# artik530_carrierboard.net
KiCad netlist of a schematic drawn in EAGLE
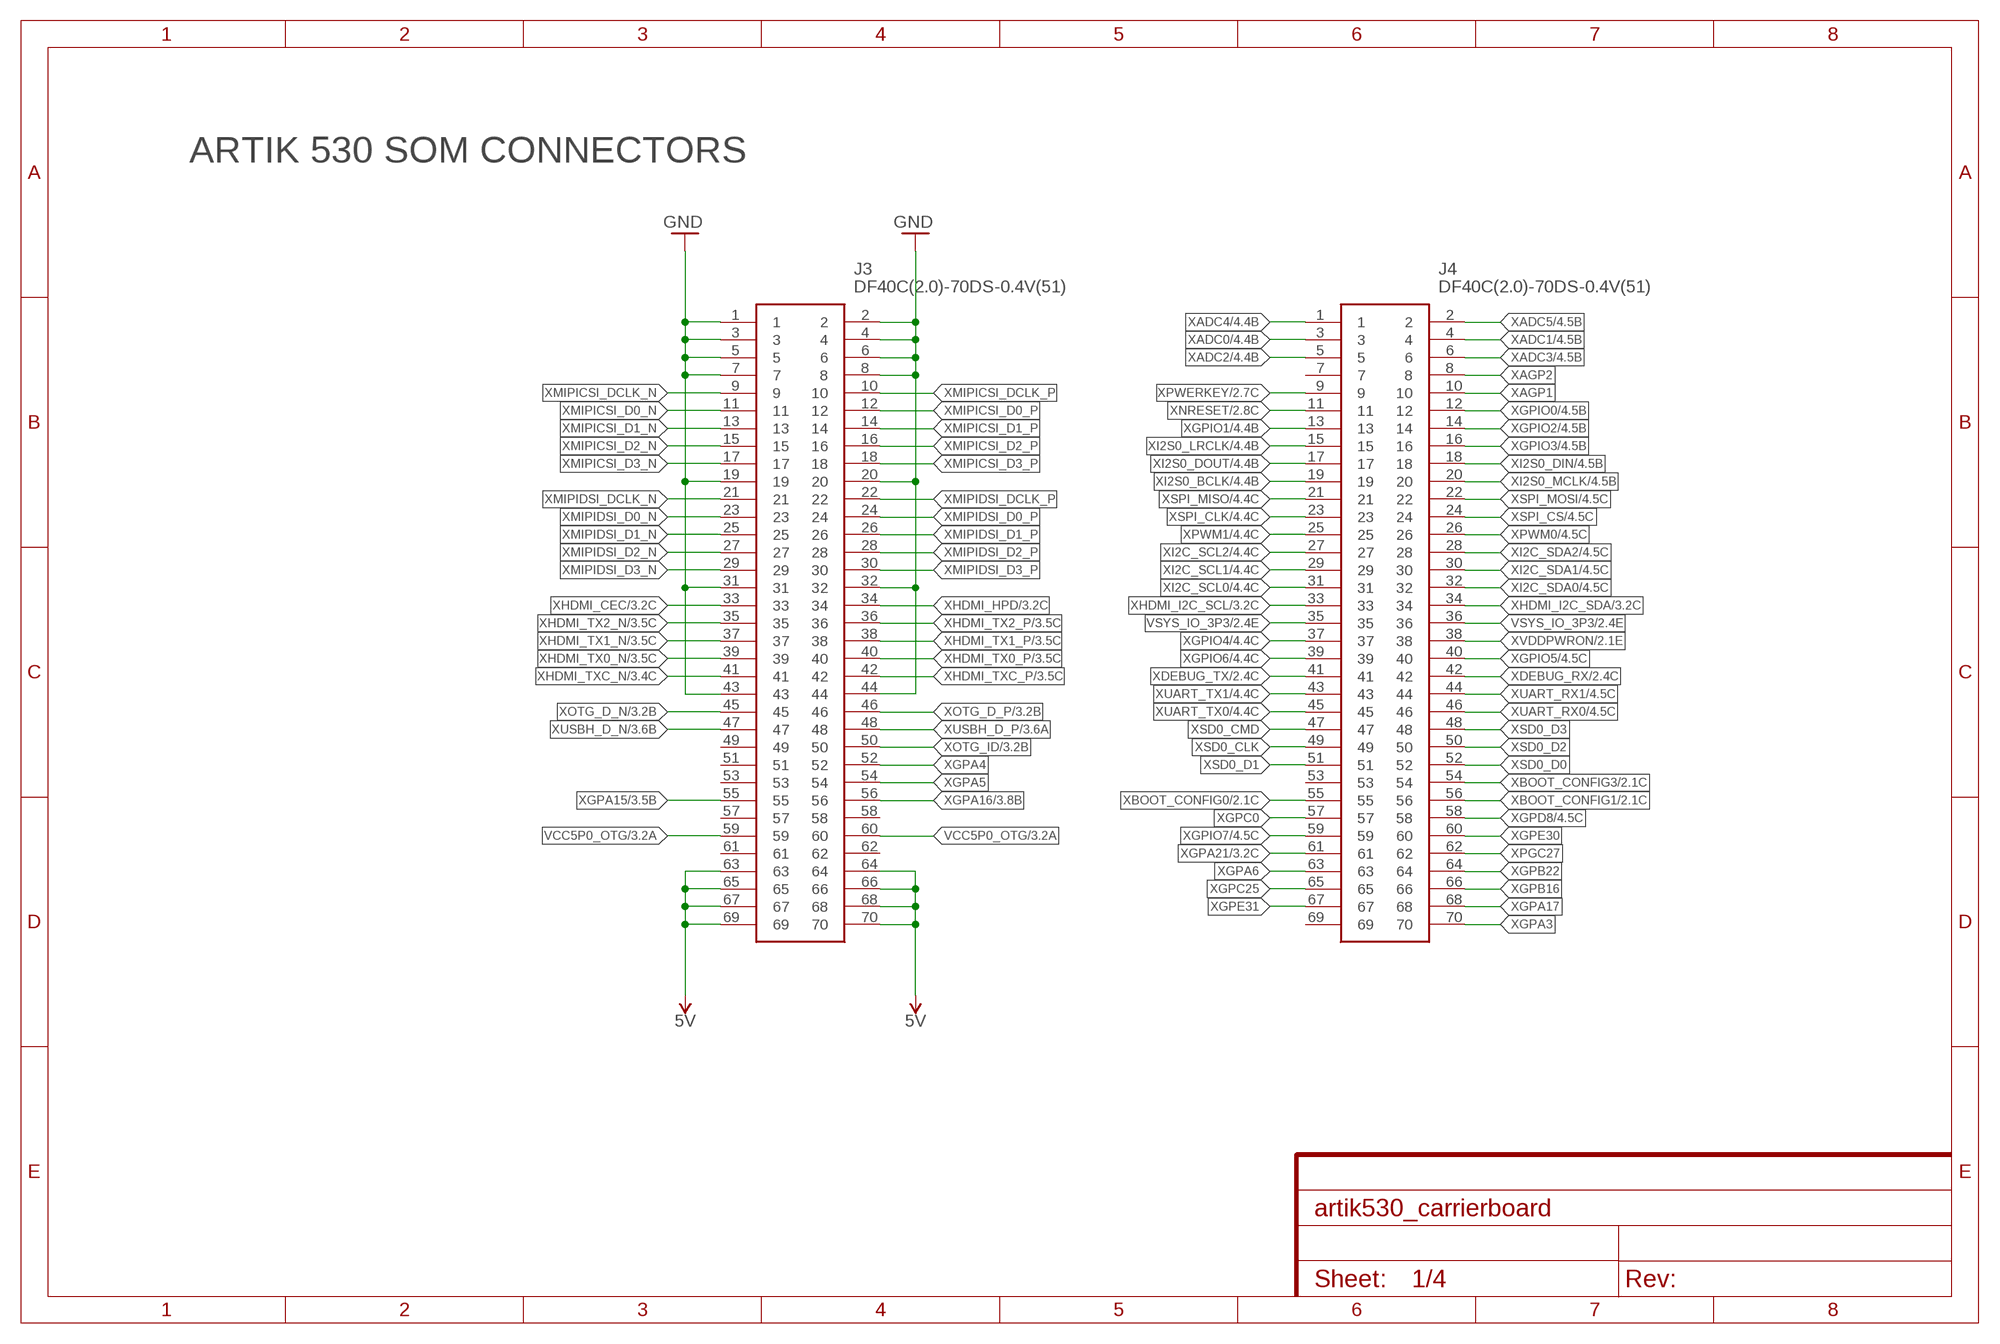
[diagram p0: schematic, sheet 1]
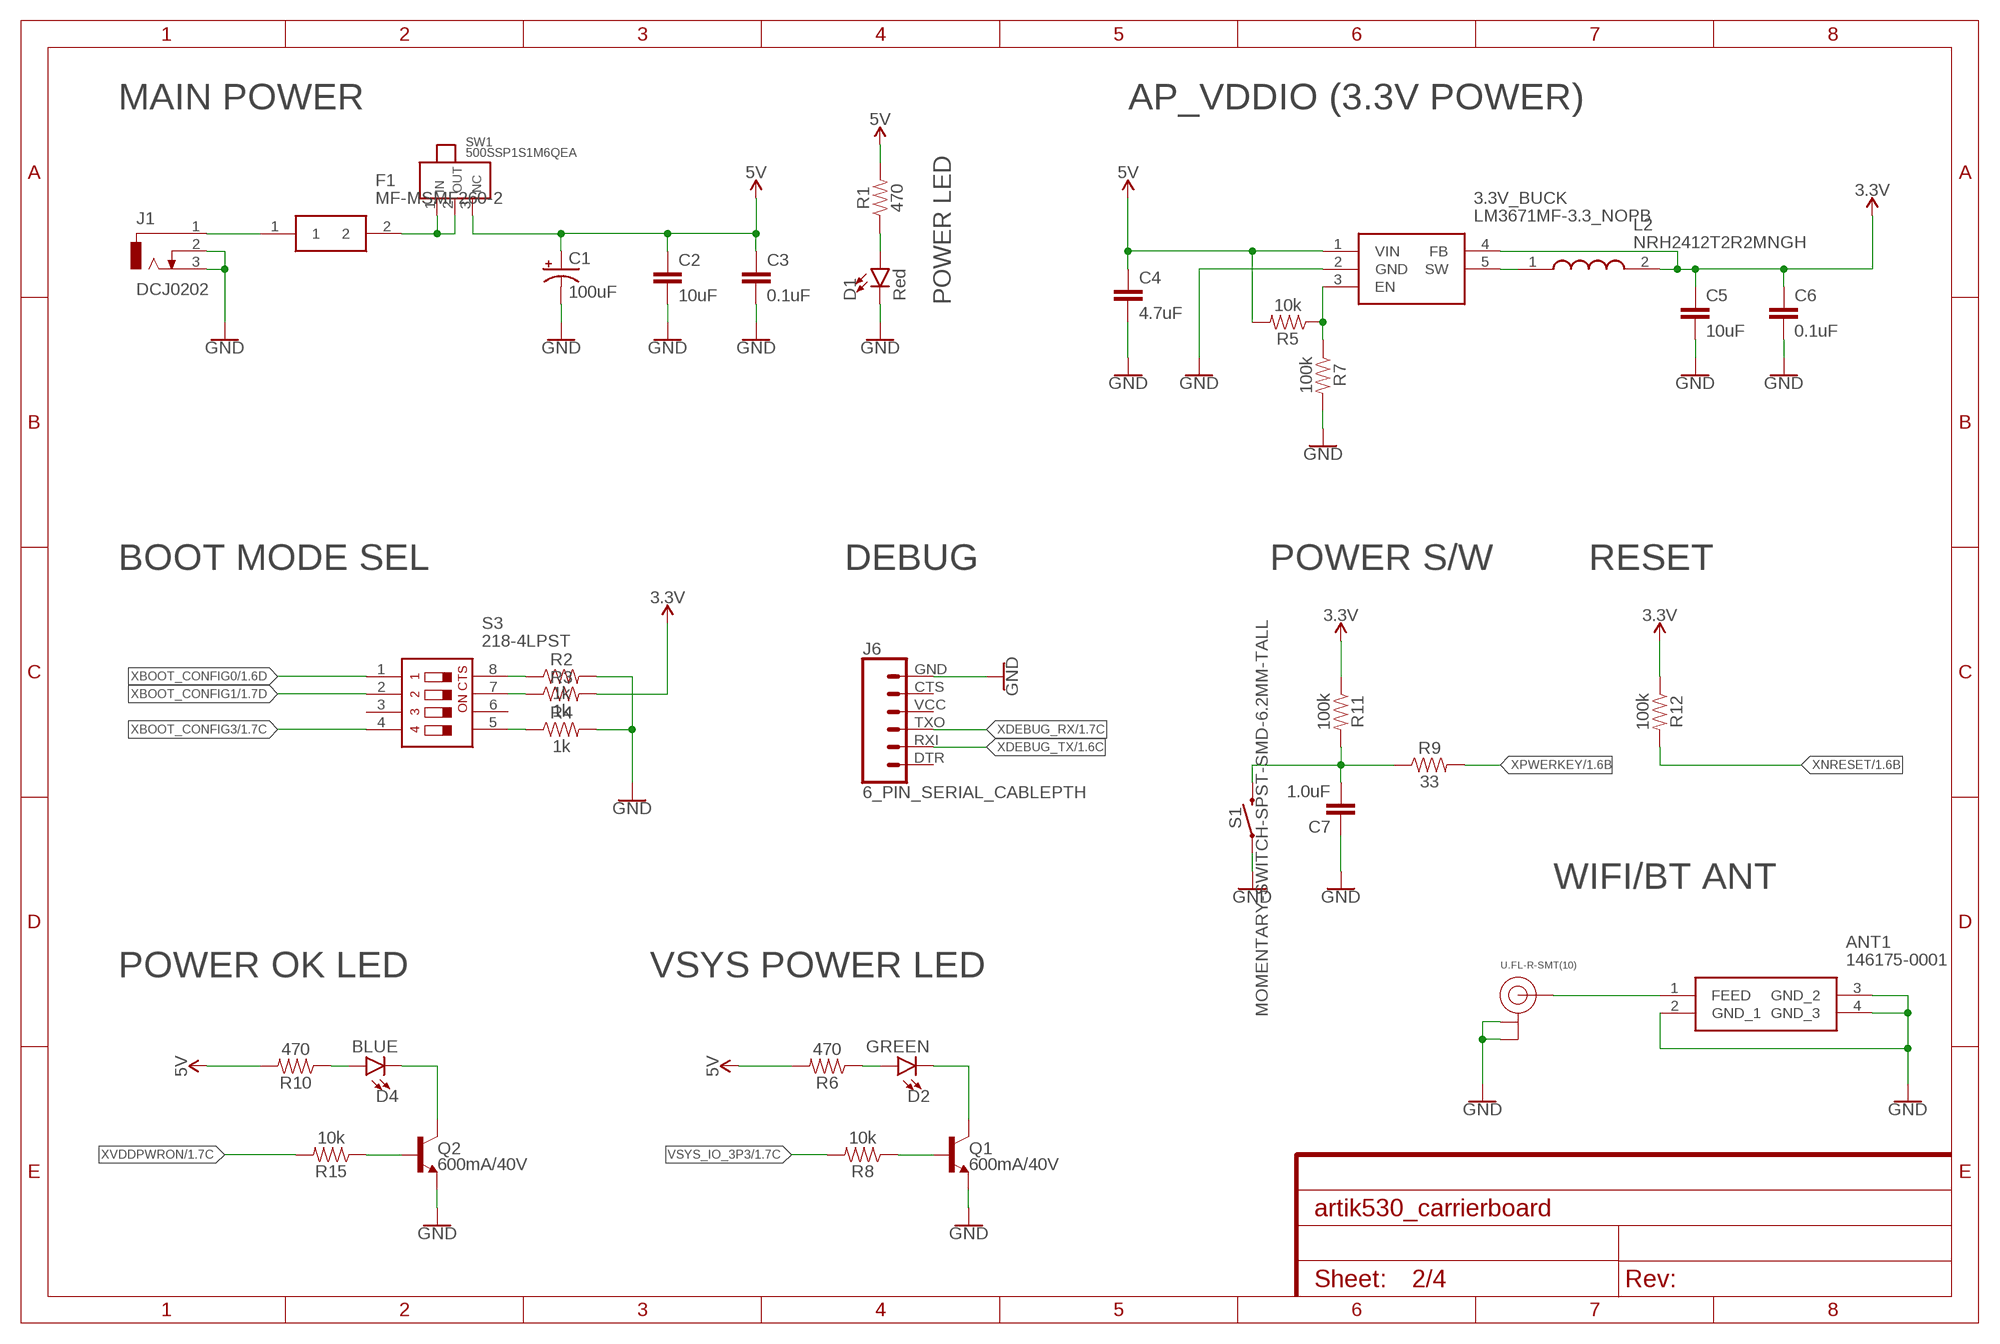
[diagram p1: schematic, sheet 2]
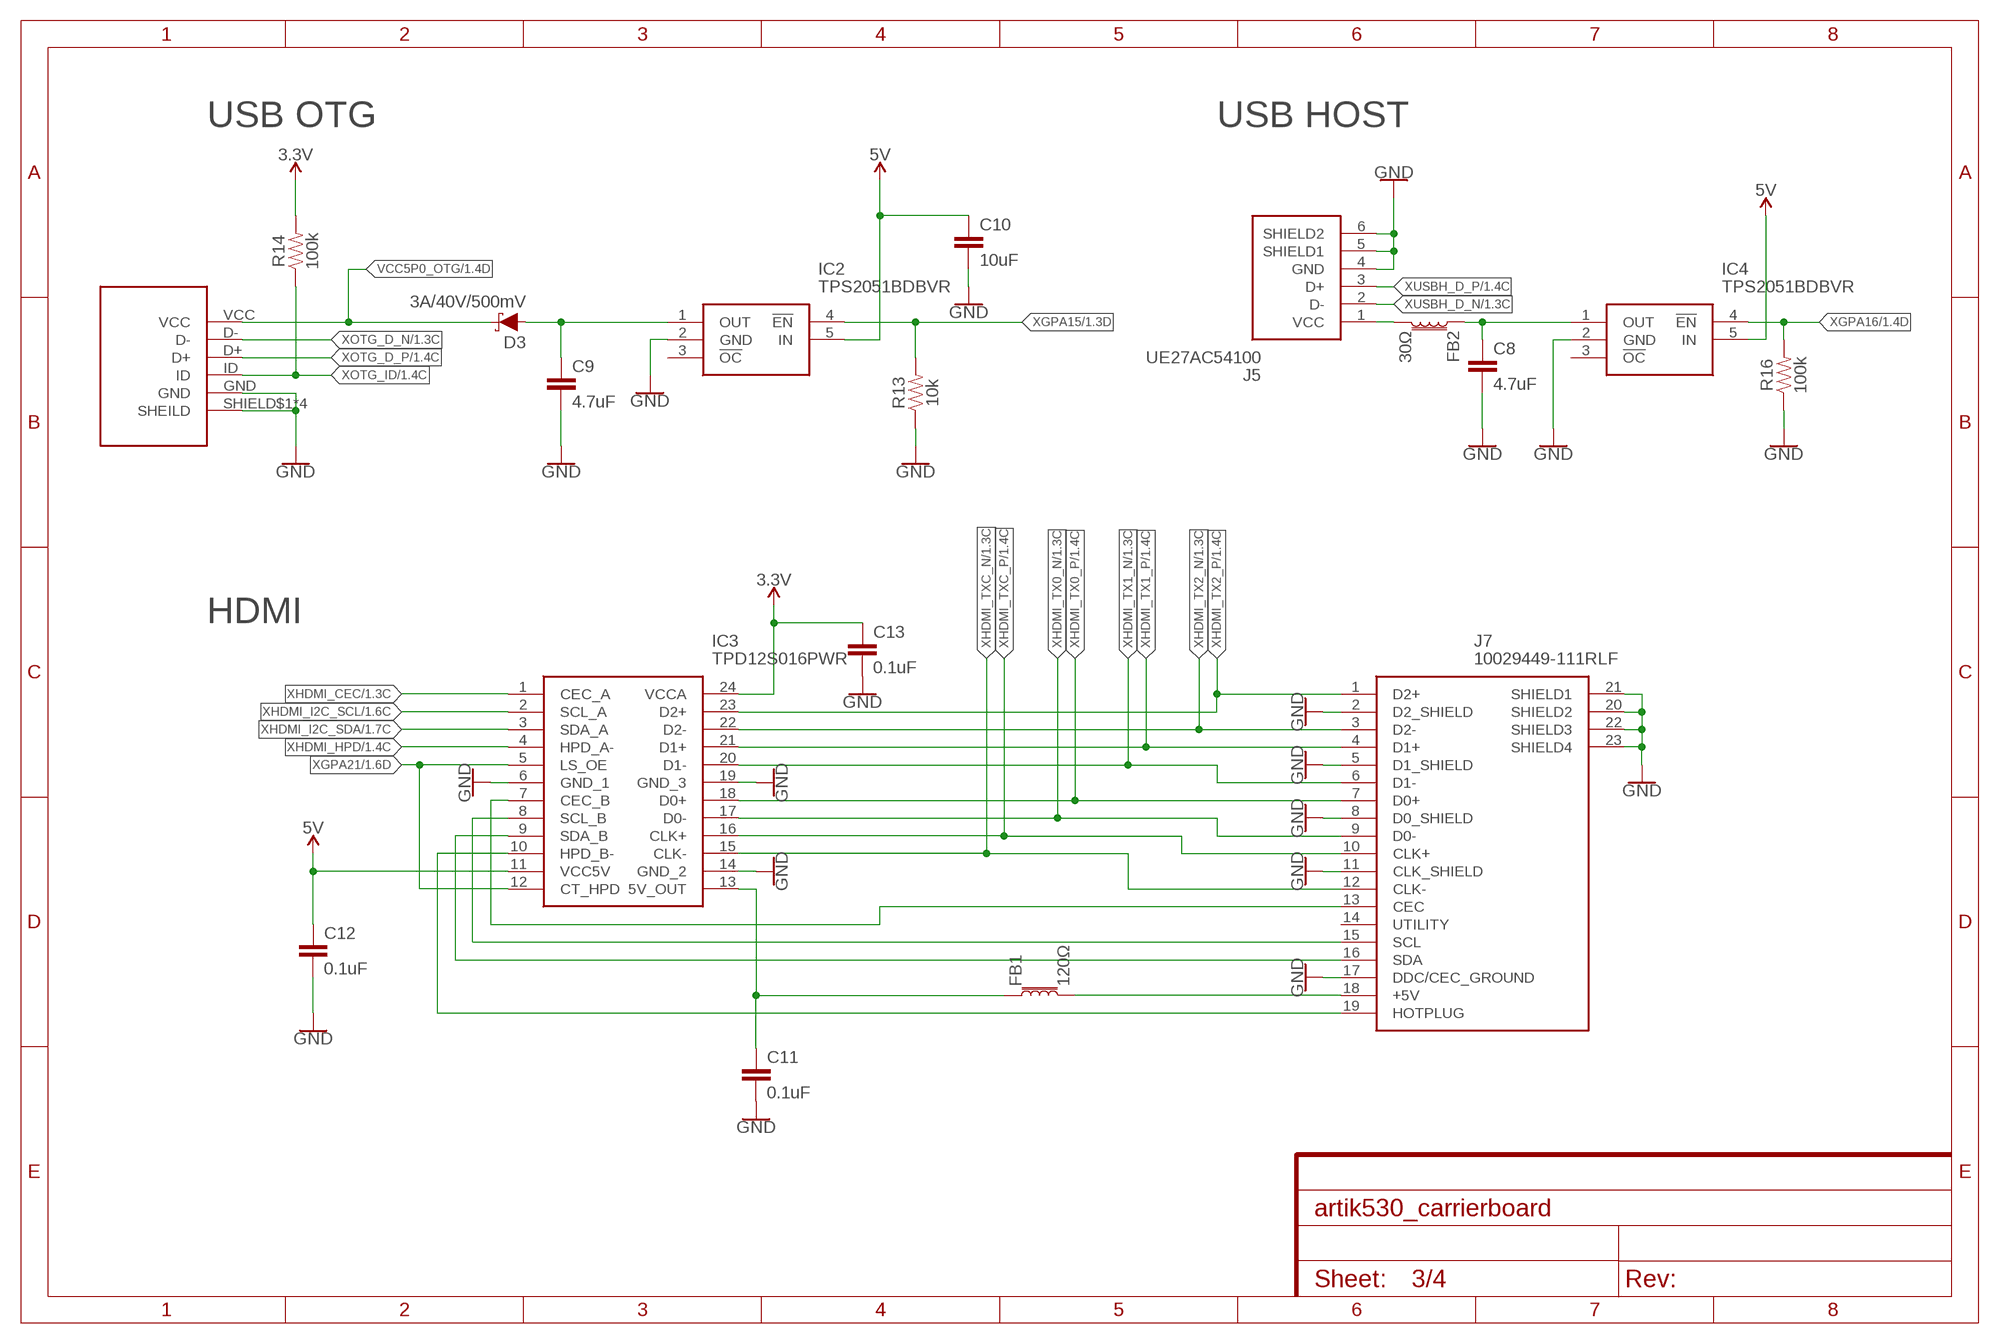
[diagram p2: schematic, sheet 3]
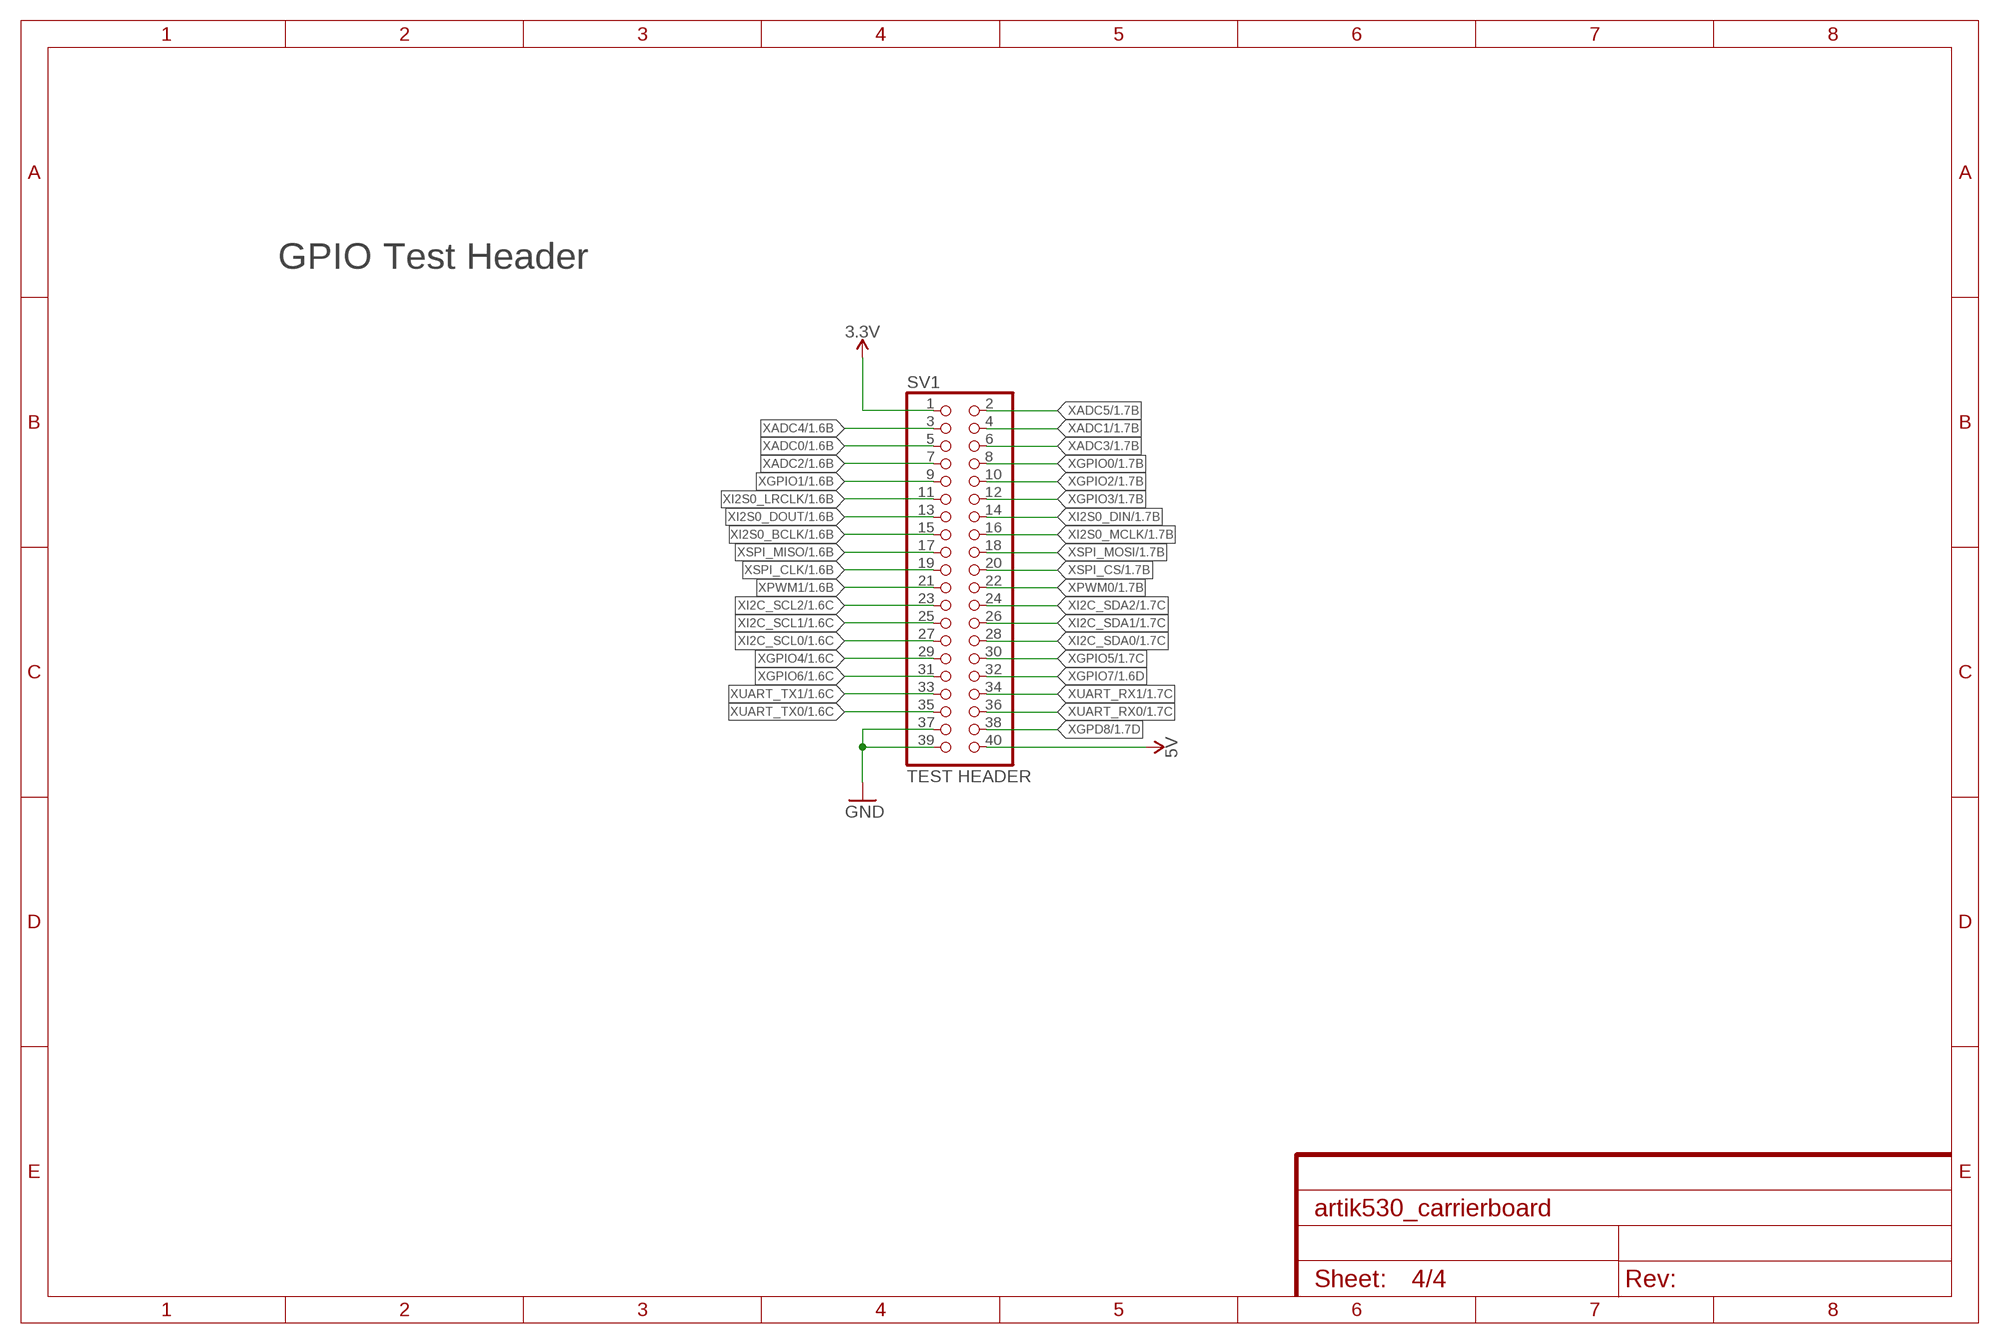
[diagram p3: schematic, sheet 4]

(export (version "E")
  (design (tool "Eeschema 10.0.6"))
  (components
    (comp (ref "3.3V_BUCK")
      (value "LM3671MF-3.3_NOPB")
      (footprint "eagle-import:SOT95P284X122-5N")
      (fields
        (field (name "DIGIKEY_PART_NUMBER") "LM3671MF-3.3/NOPBTR-ND")
        (field (name "MANUFACTURER_PART_NUMBER") "LM3671MF-3.3/NOPB")
      )
      (libsource (lib "eagle-import") (part "LM3671MF-3.3_NOPB"))
    )
    (comp (ref "ANT1")
      (value "146175-0001")
      (footprint "eagle-import:146175-0001")
      (libsource (lib "eagle-import") (part "146175-0001"))
    )
    (comp (ref "C1")
      (value "100uF")
      (footprint "eagle-import:EIA7343")
      (libsource (lib "eagle-import") (part "100UF-POLAR-EIA7343-10V-10%(TANT)"))
    )
    (comp (ref "C2")
      (value "10uF")
      (footprint "eagle-import:0603")
      (libsource (lib "eagle-import") (part "10UF-0603-6.3V-20%"))
    )
    (comp (ref "C3")
      (value "0.1uF")
      (footprint "eagle-import:0603")
      (libsource (lib "eagle-import") (part "0.1UF-0603-25V-(+80/-20%)"))
    )
    (comp (ref "C4")
      (value "4.7uF")
      (footprint "eagle-import:0603")
      (libsource (lib "eagle-import") (part "4.7UF-0603-6.3V-(10%)"))
    )
    (comp (ref "C5")
      (value "10uF")
      (footprint "eagle-import:0603")
      (libsource (lib "eagle-import") (part "10UF-0603-6.3V-20%"))
    )
    (comp (ref "C6")
      (value "0.1uF")
      (footprint "eagle-import:0603")
      (libsource (lib "eagle-import") (part "0.1UF-0603-25V-(+80/-20%)"))
    )
    (comp (ref "C7")
      (value "1.0uF")
      (footprint "eagle-import:0603")
      (libsource (lib "eagle-import") (part "1.0UF-0603-16V-10%"))
    )
    (comp (ref "D1")
      (value "Red")
      (footprint "eagle-import:LED-0603")
      (libsource (lib "eagle-import") (part "LED-RED0603-SMART"))
    )
    (comp (ref "D2")
      (value "GREEN")
      (footprint "eagle-import:LED-0603")
      (libsource (lib "eagle-import") (part "LED-GREEN0603"))
    )
    (comp (ref "D4")
      (value "BLUE")
      (footprint "eagle-import:LED-0603")
      (libsource (lib "eagle-import") (part "LED-GREEN0603"))
    )
    (comp (ref "F1")
      (value "MF-MSMF260-2")
      (footprint "eagle-import:MF-MSMF260-2")
      (fields (field (name "RS_PART_NUMBER") "6478257P"))
      (libsource (lib "eagle-import") (part "MF-MSMF260-2"))
    )
    (comp (ref "J1")
      (value "DCJ0202")
      (footprint "eagle-import:DCJ0202")
      (libsource (lib "eagle-import") (part "DCJ0202"))
    )
    (comp (ref "J6")
      (value "6_PIN_SERIAL_CABLEPTH")
      (footprint "eagle-import:FTDI_BASIC")
      (libsource (lib "eagle-import") (part "6_PIN_SERIAL_CABLEPTH"))
    )
    (comp (ref "L2")
      (value "NRH2412T2R2MNGH")
      (footprint "eagle-import:NRH2412T2R2MNGH")
      (libsource (lib "eagle-import") (part "NRH2412T2R2MNGH"))
    )
    (comp (ref "Q1")
      (value "600mA/40V")
      (footprint "eagle-import:SOT23-3")
      (libsource (lib "eagle-import") (part "TRANS_NPN-MMBT2222AL"))
    )
    (comp (ref "Q2")
      (value "600mA/40V")
      (footprint "eagle-import:SOT23-3")
      (libsource (lib "eagle-import") (part "TRANS_NPN-MMBT2222AL"))
    )
    (comp (ref "R1")
      (value "470")
      (footprint "eagle-import:0603")
      (libsource (lib "eagle-import") (part "470OHM-0603-1/10W-1%"))
    )
    (comp (ref "R2")
      (value "1k")
      (footprint "eagle-import:0603")
      (libsource (lib "eagle-import") (part "1KOHM-0603-1/10W-1%"))
    )
    (comp (ref "R3")
      (value "1k")
      (footprint "eagle-import:0603")
      (libsource (lib "eagle-import") (part "1KOHM-0603-1/10W-1%"))
    )
    (comp (ref "R4")
      (value "1k")
      (footprint "eagle-import:0603")
      (libsource (lib "eagle-import") (part "1KOHM-0603-1/10W-1%"))
    )
    (comp (ref "R5")
      (value "10k")
      (footprint "eagle-import:0603")
      (libsource (lib "eagle-import") (part "10KOHM-0603-1/10W-1%"))
    )
    (comp (ref "R6")
      (value "470")
      (footprint "eagle-import:0603")
      (libsource (lib "eagle-import") (part "470OHM-0603-1/10W-1%"))
    )
    (comp (ref "R7")
      (value "100k")
      (footprint "eagle-import:0603")
      (libsource (lib "eagle-import") (part "100KOHM-0603-1/10W-1%"))
    )
    (comp (ref "R8")
      (value "10k")
      (footprint "eagle-import:0603")
      (libsource (lib "eagle-import") (part "10KOHM-0603-1/10W-1%"))
    )
    (comp (ref "R9")
      (value "33")
      (footprint "eagle-import:0603")
      (libsource (lib "eagle-import") (part "33OHM-0603-1/10W-1%"))
    )
    (comp (ref "R10")
      (value "470")
      (footprint "eagle-import:0603")
      (libsource (lib "eagle-import") (part "470OHM-0603-1/10W-1%"))
    )
    (comp (ref "R11")
      (value "100k")
      (footprint "eagle-import:0603")
      (libsource (lib "eagle-import") (part "100KOHM-0603-1/10W-1%"))
    )
    (comp (ref "R12")
      (value "100k")
      (footprint "eagle-import:0603")
      (libsource (lib "eagle-import") (part "100KOHM-0603-1/10W-1%"))
    )
    (comp (ref "R15")
      (value "10k")
      (footprint "eagle-import:0603")
      (libsource (lib "eagle-import") (part "10KOHM-0603-1/10W-1%"))
    )
    (comp (ref "S1")
      (value "MOMENTARY-SWITCH-SPST-SMD-6.2MM-TALL")
      (footprint "eagle-import:TACTILE_SWITCH_SMD_6.2MM_TALL")
      (libsource (lib "eagle-import") (part "MOMENTARY-SWITCH-SPST-SMD-6.2MM-TALL"))
    )
    (comp (ref "S3")
      (value "218-4LPST")
      (footprint "eagle-import:SOIC127P844X265-8N")
      (libsource (lib "eagle-import") (part "218-4LPST"))
    )
    (comp (ref "SW1")
      (value "500SSP1S1M6QEA")
      (footprint "eagle-import:500SSP1S1M6QEA")
      (libsource (lib "eagle-import") (part "500SSP1S1M6QEA"))
    )
    (comp (ref "U$3")
      (value "U.FL-R-SMT(10)")
      (footprint "eagle-import:U.FL-R-SMT(10)")
      (libsource (lib "eagle-import") (part "U.FL-R-SMT(10)"))
    )
    (comp (ref "C8")
      (value "4.7uF")
      (footprint "eagle-import:0603")
      (libsource (lib "eagle-import") (part "4.7UF-0603-6.3V-(10%)"))
    )
    (comp (ref "C9")
      (value "4.7uF")
      (footprint "eagle-import:0603")
      (libsource (lib "eagle-import") (part "4.7UF-0603-6.3V-(10%)"))
    )
    (comp (ref "C10")
      (value "10uF")
      (footprint "eagle-import:0603")
      (libsource (lib "eagle-import") (part "10UF-0603-6.3V-20%"))
    )
    (comp (ref "C11")
      (value "0.1uF")
      (footprint "eagle-import:0603")
      (libsource (lib "eagle-import") (part "0.1UF-0603-25V-(+80/-20%)"))
    )
    (comp (ref "C12")
      (value "0.1uF")
      (footprint "eagle-import:0603")
      (libsource (lib "eagle-import") (part "0.1UF-0603-25V-(+80/-20%)"))
    )
    (comp (ref "C13")
      (value "0.1uF")
      (footprint "eagle-import:0603")
      (libsource (lib "eagle-import") (part "0.1UF-0603-25V-(+80/-20%)"))
    )
    (comp (ref "D3")
      (value "3A/40V/500mV")
      (footprint "eagle-import:SMA-DIODE")
      (libsource (lib "eagle-import") (part "DIODE-SCHOTTKY-B340A"))
    )
    (comp (ref "FB1")
      (value "120Ω")
      (footprint "eagle-import:0603")
      (libsource (lib "eagle-import") (part "FERRITE_BEAD-0603"))
    )
    (comp (ref "FB2")
      (value "30Ω")
      (footprint "eagle-import:0603")
      (libsource (lib "eagle-import") (part "FERRITE_BEAD-0603"))
    )
    (comp (ref "IC2")
      (value "TPS2051BDBVR")
      (footprint "eagle-import:SOT95P280X145-5N")
      (libsource (lib "eagle-import") (part "TPS2051BDBVR"))
    )
    (comp (ref "IC3")
      (value "TPD12S016PWR")
      (footprint "eagle-import:SOP65P640X120-24N")
      (fields (field (name "RS_PART_NUMBER") "1627865"))
      (libsource (lib "eagle-import") (part "TPD12S016PWR"))
    )
    (comp (ref "IC4")
      (value "TPS2051BDBVR")
      (footprint "eagle-import:SOT95P280X145-5N")
      (libsource (lib "eagle-import") (part "TPS2051BDBVR"))
    )
    (comp (ref "J2")
      (value "10118193-0001LF")
      (footprint "eagle-import:10118193-0001LF")
      (libsource (lib "eagle-import") (part "10118193-0001LF"))
    )
    (comp (ref "J5")
      (value "UE27AC54100")
      (footprint "eagle-import:UE27AC54100")
      (libsource (lib "eagle-import") (part "UE27AC54100"))
    )
    (comp (ref "J7")
      (value "10029449-111RLF")
      (footprint "eagle-import:10029449-111RLF_1")
      (libsource (lib "eagle-import") (part "10029449-111RLF"))
    )
    (comp (ref "R13")
      (value "10k")
      (footprint "eagle-import:0603")
      (libsource (lib "eagle-import") (part "10KOHM-0603-1/10W-1%"))
    )
    (comp (ref "R14")
      (value "100k")
      (footprint "eagle-import:0603")
      (libsource (lib "eagle-import") (part "100KOHM-0603-1/10W-1%"))
    )
    (comp (ref "R16")
      (value "100k")
      (footprint "eagle-import:0603")
      (libsource (lib "eagle-import") (part "100KOHM-0603-1/10W-1%"))
    )
    (comp (ref "SV1")
      (value "TEST HEADER")
      (footprint "eagle-import:2X20")
      (libsource (lib "eagle-import") (part "PINHD-2X20"))
    )
    (comp (ref "J3")
      (value "DF40C(2.0)-70DS-0.4V(51)")
      (footprint "eagle-import:DF40C(2.0)-70DS-0.4V(51)")
      (libsource (lib "eagle-import") (part "DF40C(2.0)-70DS-0.4V(51)"))
    )
    (comp (ref "J4")
      (value "DF40C(2.0)-70DS-0.4V(51)")
      (footprint "eagle-import:DF40C(2.0)-70DS-0.4V(51)")
      (libsource (lib "eagle-import") (part "DF40C(2.0)-70DS-0.4V(51)"))
    )
  )
  (nets
    (net (code "1") (name "3.3V") (class "Default")
      (node (ref "3.3V_BUCK") (pin "4") (pinfunction "FB_4") (pintype "bidirectional"))
      (node (ref "C13") (pin "1") (pinfunction "1_1") (pintype "passive"))
      (node (ref "C5") (pin "1") (pinfunction "1_1") (pintype "passive"))
      (node (ref "C6") (pin "1") (pinfunction "1_1") (pintype "passive"))
      (node (ref "IC3") (pin "24") (pinfunction "VCCA_24") (pintype "bidirectional"))
      (node (ref "L2") (pin "2") (pinfunction "2_2") (pintype "bidirectional"))
      (node (ref "R11") (pin "1") (pinfunction "1_1") (pintype "passive"))
      (node (ref "R12") (pin "1") (pinfunction "1_1") (pintype "passive"))
      (node (ref "R14") (pin "2") (pinfunction "2_2") (pintype "passive"))
      (node (ref "R3") (pin "2") (pinfunction "2_2") (pintype "passive"))
      (node (ref "SV1") (pin "1") (pinfunction "1_1") (pintype "passive"))
    )
    (net (code "2") (name "5V") (class "Default")
      (node (ref "3.3V_BUCK") (pin "1") (pinfunction "VIN_1") (pintype "bidirectional"))
      (node (ref "C1") (pin "A") (pinfunction "+_A") (pintype "passive"))
      (node (ref "C10") (pin "1") (pinfunction "1_1") (pintype "passive"))
      (node (ref "C12") (pin "1") (pinfunction "1_1") (pintype "passive"))
      (node (ref "C2") (pin "1") (pinfunction "1_1") (pintype "passive"))
      (node (ref "C3") (pin "1") (pinfunction "1_1") (pintype "passive"))
      (node (ref "C4") (pin "1") (pinfunction "1_1") (pintype "passive"))
      (node (ref "IC2") (pin "5") (pinfunction "IN_5") (pintype "input"))
      (node (ref "IC3") (pin "11") (pinfunction "VCC5V_11") (pintype "bidirectional"))
      (node (ref "IC4") (pin "5") (pinfunction "IN_5") (pintype "input"))
      (node (ref "J3") (pin "63") (pinfunction "63_63") (pintype "bidirectional"))
      (node (ref "J3") (pin "64") (pinfunction "64_64") (pintype "bidirectional"))
      (node (ref "J3") (pin "65") (pinfunction "65_65") (pintype "bidirectional"))
      (node (ref "J3") (pin "66") (pinfunction "66_66") (pintype "bidirectional"))
      (node (ref "J3") (pin "67") (pinfunction "67_67") (pintype "bidirectional"))
      (node (ref "J3") (pin "68") (pinfunction "68_68") (pintype "bidirectional"))
      (node (ref "J3") (pin "69") (pinfunction "69_69") (pintype "bidirectional"))
      (node (ref "J3") (pin "70") (pinfunction "70_70") (pintype "bidirectional"))
      (node (ref "R1") (pin "2") (pinfunction "2_2") (pintype "passive"))
      (node (ref "R10") (pin "2") (pinfunction "2_2") (pintype "passive"))
      (node (ref "R5") (pin "2") (pinfunction "2_2") (pintype "passive"))
      (node (ref "R6") (pin "2") (pinfunction "2_2") (pintype "passive"))
      (node (ref "SV1") (pin "40") (pinfunction "40_40") (pintype "passive"))
      (node (ref "SW1") (pin "3") (pinfunction "NC_3") (pintype "bidirectional"))
    )
    (net (code "3") (name "GND") (class "Default")
      (node (ref "3.3V_BUCK") (pin "2") (pinfunction "GND_2") (pintype "bidirectional"))
      (node (ref "ANT1") (pin "2") (pinfunction "GND_1_2") (pintype "bidirectional"))
      (node (ref "ANT1") (pin "3") (pinfunction "GND_2_3") (pintype "bidirectional"))
      (node (ref "ANT1") (pin "4") (pinfunction "GND_3_4") (pintype "bidirectional"))
      (node (ref "C1") (pin "C") (pinfunction "-_C") (pintype "passive"))
      (node (ref "C10") (pin "2") (pinfunction "2_2") (pintype "passive"))
      (node (ref "C11") (pin "2") (pinfunction "2_2") (pintype "passive"))
      (node (ref "C12") (pin "2") (pinfunction "2_2") (pintype "passive"))
      (node (ref "C13") (pin "2") (pinfunction "2_2") (pintype "passive"))
      (node (ref "C2") (pin "2") (pinfunction "2_2") (pintype "passive"))
      (node (ref "C3") (pin "2") (pinfunction "2_2") (pintype "passive"))
      (node (ref "C4") (pin "2") (pinfunction "2_2") (pintype "passive"))
      (node (ref "C5") (pin "2") (pinfunction "2_2") (pintype "passive"))
      (node (ref "C6") (pin "2") (pinfunction "2_2") (pintype "passive"))
      (node (ref "C7") (pin "1") (pinfunction "1_1") (pintype "passive"))
      (node (ref "C8") (pin "2") (pinfunction "2_2") (pintype "passive"))
      (node (ref "C9") (pin "2") (pinfunction "2_2") (pintype "passive"))
      (node (ref "D1") (pin "C") (pinfunction "C_C") (pintype "passive"))
      (node (ref "IC2") (pin "2") (pinfunction "GND_2") (pintype "power_in"))
      (node (ref "IC3") (pin "14") (pinfunction "GND_2_14") (pintype "bidirectional"))
      (node (ref "IC3") (pin "19") (pinfunction "GND_3_19") (pintype "bidirectional"))
      (node (ref "IC3") (pin "6") (pinfunction "GND_1_6") (pintype "bidirectional"))
      (node (ref "IC4") (pin "2") (pinfunction "GND_2") (pintype "power_in"))
      (node (ref "J1") (pin "2") (pinfunction "2_2") (pintype "passive"))
      (node (ref "J1") (pin "3") (pinfunction "3_3") (pintype "passive"))
      (node (ref "J2") (pin "GND") (pinfunction "GND_GND") (pintype "bidirectional"))
      (node (ref "J2") (pin "SHIELD$1") (pinfunction "SHEILD_SHIELD$1") (pintype "bidirectional"))
      (node (ref "J2") (pin "SHIELD$2") (pinfunction "SHEILD_SHIELD$2") (pintype "bidirectional"))
      (node (ref "J2") (pin "SHIELD$3") (pinfunction "SHEILD_SHIELD$3") (pintype "bidirectional"))
      (node (ref "J2") (pin "SHIELD$4") (pinfunction "SHEILD_SHIELD$4") (pintype "bidirectional"))
      (node (ref "J3") (pin "1") (pinfunction "1_1") (pintype "bidirectional"))
      (node (ref "J3") (pin "19") (pinfunction "19_19") (pintype "bidirectional"))
      (node (ref "J3") (pin "2") (pinfunction "2_2") (pintype "bidirectional"))
      (node (ref "J3") (pin "20") (pinfunction "20_20") (pintype "bidirectional"))
      (node (ref "J3") (pin "3") (pinfunction "3_3") (pintype "bidirectional"))
      (node (ref "J3") (pin "31") (pinfunction "31_31") (pintype "bidirectional"))
      (node (ref "J3") (pin "32") (pinfunction "32_32") (pintype "bidirectional"))
      (node (ref "J3") (pin "4") (pinfunction "4_4") (pintype "bidirectional"))
      (node (ref "J3") (pin "43") (pinfunction "43_43") (pintype "bidirectional"))
      (node (ref "J3") (pin "44") (pinfunction "44_44") (pintype "bidirectional"))
      (node (ref "J3") (pin "5") (pinfunction "5_5") (pintype "bidirectional"))
      (node (ref "J3") (pin "6") (pinfunction "6_6") (pintype "bidirectional"))
      (node (ref "J3") (pin "7") (pinfunction "7_7") (pintype "bidirectional"))
      (node (ref "J3") (pin "8") (pinfunction "8_8") (pintype "bidirectional"))
      (node (ref "J5") (pin "4") (pinfunction "GND_4") (pintype "bidirectional"))
      (node (ref "J5") (pin "5") (pinfunction "SHIELD1_5") (pintype "bidirectional"))
      (node (ref "J5") (pin "6") (pinfunction "SHIELD2_6") (pintype "bidirectional"))
      (node (ref "J6") (pin "GND") (pinfunction "6_GND") (pintype "passive"))
      (node (ref "J7") (pin "11") (pinfunction "CLK_SHIELD_11") (pintype "bidirectional"))
      (node (ref "J7") (pin "17") (pinfunction "DDC/CEC_GROUND_17") (pintype "bidirectional"))
      (node (ref "J7") (pin "2") (pinfunction "D2_SHIELD_2") (pintype "bidirectional"))
      (node (ref "J7") (pin "20") (pinfunction "SHIELD2_20") (pintype "bidirectional"))
      (node (ref "J7") (pin "21") (pinfunction "SHIELD1_21") (pintype "bidirectional"))
      (node (ref "J7") (pin "22") (pinfunction "SHIELD3_22") (pintype "bidirectional"))
      (node (ref "J7") (pin "23") (pinfunction "SHIELD4_23") (pintype "bidirectional"))
      (node (ref "J7") (pin "5") (pinfunction "D1_SHIELD_5") (pintype "bidirectional"))
      (node (ref "J7") (pin "8") (pinfunction "D0_SHIELD_8") (pintype "bidirectional"))
      (node (ref "Q1") (pin "2") (pinfunction "E_2") (pintype "passive"))
      (node (ref "Q2") (pin "2") (pinfunction "E_2") (pintype "passive"))
      (node (ref "R13") (pin "1") (pinfunction "1_1") (pintype "passive"))
      (node (ref "R16") (pin "1") (pinfunction "1_1") (pintype "passive"))
      (node (ref "R2") (pin "2") (pinfunction "2_2") (pintype "passive"))
      (node (ref "R4") (pin "2") (pinfunction "2_2") (pintype "passive"))
      (node (ref "R7") (pin "2") (pinfunction "2_2") (pintype "passive"))
      (node (ref "S1") (pin "A2") (pinfunction "1_A2") (pintype "passive"))
      (node (ref "SV1") (pin "37") (pinfunction "37_37") (pintype "passive"))
      (node (ref "SV1") (pin "39") (pinfunction "39_39") (pintype "passive"))
      (node (ref "U$3") (pin "1") (pinfunction "GND1_1") (pintype "bidirectional"))
      (node (ref "U$3") (pin "2") (pinfunction "GND2_2") (pintype "bidirectional"))
    )
    (net (code "4") (name "Net-(3.3V_BUCK-EN)") (class "Default")
      (node (ref "3.3V_BUCK") (pin "3") (pinfunction "EN_3") (pintype "bidirectional"))
      (node (ref "R5") (pin "1") (pinfunction "1_1") (pintype "passive"))
      (node (ref "R7") (pin "1") (pinfunction "1_1") (pintype "passive"))
    )
    (net (code "5") (name "Net-(3.3V_BUCK-SW)") (class "Default")
      (node (ref "3.3V_BUCK") (pin "5") (pinfunction "SW_5") (pintype "bidirectional"))
      (node (ref "L2") (pin "1") (pinfunction "1_1") (pintype "bidirectional"))
    )
    (net (code "6") (name "Net-(ANT1-FEED)") (class "Default")
      (node (ref "ANT1") (pin "1") (pinfunction "FEED_1") (pintype "bidirectional"))
      (node (ref "U$3") (pin "3") (pinfunction "SIG_3") (pintype "bidirectional"))
    )
    (net (code "7") (name "Net-(D1-PadA)") (class "Default")
      (node (ref "D1") (pin "A") (pinfunction "A_A") (pintype "passive"))
      (node (ref "R1") (pin "1") (pinfunction "1_1") (pintype "passive"))
    )
    (net (code "8") (name "Net-(D2-PadA)") (class "Default")
      (node (ref "D2") (pin "A") (pinfunction "A_A") (pintype "passive"))
      (node (ref "R6") (pin "1") (pinfunction "1_1") (pintype "passive"))
    )
    (net (code "9") (name "Net-(D4-PadA)") (class "Default")
      (node (ref "D4") (pin "A") (pinfunction "A_A") (pintype "passive"))
      (node (ref "R10") (pin "1") (pinfunction "1_1") (pintype "passive"))
    )
    (net (code "10") (name "Net-(F1-Pad1)") (class "Default")
      (node (ref "F1") (pin "1") (pinfunction "1_1") (pintype "bidirectional"))
      (node (ref "J1") (pin "1") (pinfunction "1_1") (pintype "passive"))
    )
    (net (code "11") (name "Net-(IC2-OUT)") (class "Default")
      (node (ref "C9") (pin "1") (pinfunction "1_1") (pintype "passive"))
      (node (ref "D3") (pin "A") (pinfunction "A_A") (pintype "passive"))
      (node (ref "IC2") (pin "1") (pinfunction "OUT_1") (pintype "output"))
    )
    (net (code "12") (name "Net-(IC3-5V_OUT)") (class "Default")
      (node (ref "C11") (pin "1") (pinfunction "1_1") (pintype "passive"))
      (node (ref "FB1") (pin "1") (pinfunction "1_1") (pintype "passive"))
      (node (ref "IC3") (pin "13") (pinfunction "5V_OUT_13") (pintype "output"))
    )
    (net (code "13") (name "Net-(IC3-CEC_B)") (class "Default")
      (node (ref "IC3") (pin "7") (pinfunction "CEC_B_7") (pintype "bidirectional"))
      (node (ref "J7") (pin "13") (pinfunction "CEC_13") (pintype "bidirectional"))
    )
    (net (code "14") (name "Net-(IC3-HPD_B-)") (class "Default")
      (node (ref "IC3") (pin "10") (pinfunction "HPD_B-_10") (pintype "bidirectional"))
      (node (ref "J7") (pin "19") (pinfunction "HOTPLUG_19") (pintype "bidirectional"))
    )
    (net (code "15") (name "Net-(IC3-SCL_B)") (class "Default")
      (node (ref "IC3") (pin "8") (pinfunction "SCL_B_8") (pintype "bidirectional"))
      (node (ref "J7") (pin "15") (pinfunction "SCL_15") (pintype "bidirectional"))
    )
    (net (code "16") (name "Net-(IC3-SDA_B)") (class "Default")
      (node (ref "IC3") (pin "9") (pinfunction "SDA_B_9") (pintype "bidirectional"))
      (node (ref "J7") (pin "16") (pinfunction "SDA_16") (pintype "bidirectional"))
    )
    (net (code "17") (name "Net-(IC4-OUT)") (class "Default")
      (node (ref "C8") (pin "1") (pinfunction "1_1") (pintype "passive"))
      (node (ref "FB2") (pin "1") (pinfunction "1_1") (pintype "passive"))
      (node (ref "IC4") (pin "1") (pinfunction "OUT_1") (pintype "output"))
    )
    (net (code "18") (name "Net-(J5-VCC)") (class "Default")
      (node (ref "FB2") (pin "2") (pinfunction "2_2") (pintype "passive"))
      (node (ref "J5") (pin "1") (pinfunction "VCC_1") (pintype "bidirectional"))
    )
    (net (code "19") (name "Net-(J7-+5V)") (class "Default")
      (node (ref "FB1") (pin "2") (pinfunction "2_2") (pintype "passive"))
      (node (ref "J7") (pin "18") (pinfunction "+5V_18") (pintype "bidirectional"))
    )
    (net (code "20") (name "Net-(Q1-B)") (class "Default")
      (node (ref "Q1") (pin "1") (pinfunction "B_1") (pintype "passive"))
      (node (ref "R8") (pin "1") (pinfunction "1_1") (pintype "passive"))
    )
    (net (code "21") (name "Net-(Q1-C)") (class "Default")
      (node (ref "D2") (pin "C") (pinfunction "C_C") (pintype "passive"))
      (node (ref "Q1") (pin "3") (pinfunction "C_3") (pintype "passive"))
    )
    (net (code "22") (name "Net-(Q2-B)") (class "Default")
      (node (ref "Q2") (pin "1") (pinfunction "B_1") (pintype "passive"))
      (node (ref "R15") (pin "1") (pinfunction "1_1") (pintype "passive"))
    )
    (net (code "23") (name "Net-(Q2-C)") (class "Default")
      (node (ref "D4") (pin "C") (pinfunction "C_C") (pintype "passive"))
      (node (ref "Q2") (pin "3") (pinfunction "C_3") (pintype "passive"))
    )
    (net (code "24") (name "Net-(R2-Pad1)") (class "Default")
      (node (ref "R2") (pin "1") (pinfunction "1_1") (pintype "passive"))
      (node (ref "S3") (pin "8") (pinfunction "8_8") (pintype "bidirectional"))
    )
    (net (code "25") (name "Net-(R3-Pad1)") (class "Default")
      (node (ref "R3") (pin "1") (pinfunction "1_1") (pintype "passive"))
      (node (ref "S3") (pin "7") (pinfunction "7_7") (pintype "bidirectional"))
    )
    (net (code "26") (name "Net-(R4-Pad1)") (class "Default")
      (node (ref "R4") (pin "1") (pinfunction "1_1") (pintype "passive"))
      (node (ref "S3") (pin "5") (pinfunction "5_5") (pintype "bidirectional"))
    )
    (net (code "27") (name "Net-(S1-2)") (class "Default")
      (node (ref "C7") (pin "2") (pinfunction "2_2") (pintype "passive"))
      (node (ref "R11") (pin "2") (pinfunction "2_2") (pintype "passive"))
      (node (ref "R9") (pin "1") (pinfunction "1_1") (pintype "passive"))
      (node (ref "S1") (pin "B2") (pinfunction "2_B2") (pintype "passive"))
    )
    (net (code "28") (name "Net-(SW1-IN)") (class "Default")
      (node (ref "F1") (pin "2") (pinfunction "2_2") (pintype "bidirectional"))
      (node (ref "SW1") (pin "1") (pinfunction "IN_1") (pintype "bidirectional"))
      (node (ref "SW1") (pin "2") (pinfunction "OUT_2") (pintype "bidirectional"))
    )
    (net (code "29") (name "VCC5P0_OTG") (class "Default")
      (node (ref "D3") (pin "C") (pinfunction "C_C") (pintype "passive"))
      (node (ref "J2") (pin "VCC") (pinfunction "VCC_VCC") (pintype "bidirectional"))
      (node (ref "J3") (pin "59") (pinfunction "59_59") (pintype "bidirectional"))
      (node (ref "J3") (pin "60") (pinfunction "60_60") (pintype "bidirectional"))
    )
    (net (code "30") (name "VSYS_IO_3P3") (class "Default")
      (node (ref "J4") (pin "35") (pinfunction "35_35") (pintype "bidirectional"))
      (node (ref "J4") (pin "36") (pinfunction "36_36") (pintype "bidirectional"))
      (node (ref "R8") (pin "2") (pinfunction "2_2") (pintype "passive"))
    )
    (net (code "31") (name "XADC0") (class "Default")
      (node (ref "J4") (pin "3") (pinfunction "3_3") (pintype "bidirectional"))
      (node (ref "SV1") (pin "5") (pinfunction "5_5") (pintype "passive"))
    )
    (net (code "32") (name "XADC1") (class "Default")
      (node (ref "J4") (pin "4") (pinfunction "4_4") (pintype "bidirectional"))
      (node (ref "SV1") (pin "4") (pinfunction "4_4") (pintype "passive"))
    )
    (net (code "33") (name "XADC2") (class "Default")
      (node (ref "J4") (pin "5") (pinfunction "5_5") (pintype "bidirectional"))
      (node (ref "SV1") (pin "7") (pinfunction "7_7") (pintype "passive"))
    )
    (net (code "34") (name "XADC3") (class "Default")
      (node (ref "J4") (pin "6") (pinfunction "6_6") (pintype "bidirectional"))
      (node (ref "SV1") (pin "6") (pinfunction "6_6") (pintype "passive"))
    )
    (net (code "35") (name "XADC4") (class "Default")
      (node (ref "J4") (pin "1") (pinfunction "1_1") (pintype "bidirectional"))
      (node (ref "SV1") (pin "3") (pinfunction "3_3") (pintype "passive"))
    )
    (net (code "36") (name "XADC5") (class "Default")
      (node (ref "J4") (pin "2") (pinfunction "2_2") (pintype "bidirectional"))
      (node (ref "SV1") (pin "2") (pinfunction "2_2") (pintype "passive"))
    )
    (net (code "37") (name "XAGP1") (class "Default")
      (node (ref "J4") (pin "10") (pinfunction "10_10") (pintype "bidirectional"))
    )
    (net (code "38") (name "XAGP2") (class "Default")
      (node (ref "J4") (pin "8") (pinfunction "8_8") (pintype "bidirectional"))
    )
    (net (code "39") (name "XBOOT_CONFIG0") (class "Default")
      (node (ref "J4") (pin "55") (pinfunction "55_55") (pintype "bidirectional"))
      (node (ref "S3") (pin "1") (pinfunction "1_1") (pintype "bidirectional"))
    )
    (net (code "40") (name "XBOOT_CONFIG1") (class "Default")
      (node (ref "J4") (pin "56") (pinfunction "56_56") (pintype "bidirectional"))
      (node (ref "S3") (pin "2") (pinfunction "2_2") (pintype "bidirectional"))
    )
    (net (code "41") (name "XBOOT_CONFIG3") (class "Default")
      (node (ref "J4") (pin "54") (pinfunction "54_54") (pintype "bidirectional"))
      (node (ref "S3") (pin "4") (pinfunction "4_4") (pintype "bidirectional"))
    )
    (net (code "42") (name "XDEBUG_RX") (class "Default")
      (node (ref "J4") (pin "42") (pinfunction "42_42") (pintype "bidirectional"))
      (node (ref "J6") (pin "TXO") (pinfunction "3_TXO") (pintype "passive"))
    )
    (net (code "43") (name "XDEBUG_TX") (class "Default")
      (node (ref "J4") (pin "41") (pinfunction "41_41") (pintype "bidirectional"))
      (node (ref "J6") (pin "RXI") (pinfunction "2_RXI") (pintype "passive"))
    )
    (net (code "44") (name "XGPA3") (class "Default")
      (node (ref "J4") (pin "70") (pinfunction "70_70") (pintype "bidirectional"))
    )
    (net (code "45") (name "XGPA4") (class "Default")
      (node (ref "J3") (pin "52") (pinfunction "52_52") (pintype "bidirectional"))
    )
    (net (code "46") (name "XGPA5") (class "Default")
      (node (ref "J3") (pin "54") (pinfunction "54_54") (pintype "bidirectional"))
    )
    (net (code "47") (name "XGPA6") (class "Default")
      (node (ref "J4") (pin "63") (pinfunction "63_63") (pintype "bidirectional"))
    )
    (net (code "48") (name "XGPA15") (class "Default")
      (node (ref "IC2") (pin "4") (pinfunction "~{EN}_4") (pintype "bidirectional"))
      (node (ref "J3") (pin "55") (pinfunction "55_55") (pintype "bidirectional"))
      (node (ref "R13") (pin "2") (pinfunction "2_2") (pintype "passive"))
    )
    (net (code "49") (name "XGPA16") (class "Default")
      (node (ref "IC4") (pin "4") (pinfunction "~{EN}_4") (pintype "bidirectional"))
      (node (ref "J3") (pin "56") (pinfunction "56_56") (pintype "bidirectional"))
      (node (ref "R16") (pin "2") (pinfunction "2_2") (pintype "passive"))
    )
    (net (code "50") (name "XGPA17") (class "Default")
      (node (ref "J4") (pin "68") (pinfunction "68_68") (pintype "bidirectional"))
    )
    (net (code "51") (name "XGPA21") (class "Default")
      (node (ref "IC3") (pin "12") (pinfunction "CT_HPD_12") (pintype "bidirectional"))
      (node (ref "IC3") (pin "5") (pinfunction "LS_OE_5") (pintype "bidirectional"))
      (node (ref "J4") (pin "61") (pinfunction "61_61") (pintype "bidirectional"))
    )
    (net (code "52") (name "XGPB16") (class "Default")
      (node (ref "J4") (pin "66") (pinfunction "66_66") (pintype "bidirectional"))
    )
    (net (code "53") (name "XGPB22") (class "Default")
      (node (ref "J4") (pin "64") (pinfunction "64_64") (pintype "bidirectional"))
    )
    (net (code "54") (name "XGPC0") (class "Default")
      (node (ref "J4") (pin "57") (pinfunction "57_57") (pintype "bidirectional"))
    )
    (net (code "55") (name "XGPC25") (class "Default")
      (node (ref "J4") (pin "65") (pinfunction "65_65") (pintype "bidirectional"))
    )
    (net (code "56") (name "XGPD8") (class "Default")
      (node (ref "J4") (pin "58") (pinfunction "58_58") (pintype "bidirectional"))
      (node (ref "SV1") (pin "38") (pinfunction "38_38") (pintype "passive"))
    )
    (net (code "57") (name "XGPE30") (class "Default")
      (node (ref "J4") (pin "60") (pinfunction "60_60") (pintype "bidirectional"))
    )
    (net (code "58") (name "XGPE31") (class "Default")
      (node (ref "J4") (pin "67") (pinfunction "67_67") (pintype "bidirectional"))
    )
    (net (code "59") (name "XGPIO0") (class "Default")
      (node (ref "J4") (pin "12") (pinfunction "12_12") (pintype "bidirectional"))
      (node (ref "SV1") (pin "8") (pinfunction "8_8") (pintype "passive"))
    )
    (net (code "60") (name "XGPIO1") (class "Default")
      (node (ref "J4") (pin "13") (pinfunction "13_13") (pintype "bidirectional"))
      (node (ref "SV1") (pin "9") (pinfunction "9_9") (pintype "passive"))
    )
    (net (code "61") (name "XGPIO2") (class "Default")
      (node (ref "J4") (pin "14") (pinfunction "14_14") (pintype "bidirectional"))
      (node (ref "SV1") (pin "10") (pinfunction "10_10") (pintype "passive"))
    )
    (net (code "62") (name "XGPIO3") (class "Default")
      (node (ref "J4") (pin "16") (pinfunction "16_16") (pintype "bidirectional"))
      (node (ref "SV1") (pin "12") (pinfunction "12_12") (pintype "passive"))
    )
    (net (code "63") (name "XGPIO4") (class "Default")
      (node (ref "J4") (pin "37") (pinfunction "37_37") (pintype "bidirectional"))
      (node (ref "SV1") (pin "29") (pinfunction "29_29") (pintype "passive"))
    )
    (net (code "64") (name "XGPIO5") (class "Default")
      (node (ref "J4") (pin "40") (pinfunction "40_40") (pintype "bidirectional"))
      (node (ref "SV1") (pin "30") (pinfunction "30_30") (pintype "passive"))
    )
    (net (code "65") (name "XGPIO6") (class "Default")
      (node (ref "J4") (pin "39") (pinfunction "39_39") (pintype "bidirectional"))
      (node (ref "SV1") (pin "31") (pinfunction "31_31") (pintype "passive"))
    )
    (net (code "66") (name "XGPIO7") (class "Default")
      (node (ref "J4") (pin "59") (pinfunction "59_59") (pintype "bidirectional"))
      (node (ref "SV1") (pin "32") (pinfunction "32_32") (pintype "passive"))
    )
    (net (code "67") (name "XHDMI_CEC") (class "Default")
      (node (ref "IC3") (pin "1") (pinfunction "CEC_A_1") (pintype "bidirectional"))
      (node (ref "J3") (pin "33") (pinfunction "33_33") (pintype "bidirectional"))
    )
    (net (code "68") (name "XHDMI_HPD") (class "Default")
      (node (ref "IC3") (pin "4") (pinfunction "HPD_A-_4") (pintype "bidirectional"))
      (node (ref "J3") (pin "34") (pinfunction "34_34") (pintype "bidirectional"))
    )
    (net (code "69") (name "XHDMI_I2C_SCL") (class "Default")
      (node (ref "IC3") (pin "2") (pinfunction "SCL_A_2") (pintype "bidirectional"))
      (node (ref "J4") (pin "33") (pinfunction "33_33") (pintype "bidirectional"))
    )
    (net (code "70") (name "XHDMI_I2C_SDA") (class "Default")
      (node (ref "IC3") (pin "3") (pinfunction "SDA_A_3") (pintype "bidirectional"))
      (node (ref "J4") (pin "34") (pinfunction "34_34") (pintype "bidirectional"))
    )
    (net (code "71") (name "XHDMI_TX0_N") (class "Default")
      (node (ref "IC3") (pin "17") (pinfunction "D0-_17") (pintype "bidirectional"))
      (node (ref "J3") (pin "39") (pinfunction "39_39") (pintype "bidirectional"))
      (node (ref "J7") (pin "9") (pinfunction "D0-_9") (pintype "bidirectional"))
    )
    (net (code "72") (name "XHDMI_TX0_P") (class "Default")
      (node (ref "IC3") (pin "18") (pinfunction "D0+_18") (pintype "bidirectional"))
      (node (ref "J3") (pin "40") (pinfunction "40_40") (pintype "bidirectional"))
      (node (ref "J7") (pin "7") (pinfunction "D0+_7") (pintype "bidirectional"))
    )
    (net (code "73") (name "XHDMI_TX1_N") (class "Default")
      (node (ref "IC3") (pin "20") (pinfunction "D1-_20") (pintype "bidirectional"))
      (node (ref "J3") (pin "37") (pinfunction "37_37") (pintype "bidirectional"))
      (node (ref "J7") (pin "6") (pinfunction "D1-_6") (pintype "bidirectional"))
    )
    (net (code "74") (name "XHDMI_TX1_P") (class "Default")
      (node (ref "IC3") (pin "21") (pinfunction "D1+_21") (pintype "bidirectional"))
      (node (ref "J3") (pin "38") (pinfunction "38_38") (pintype "bidirectional"))
      (node (ref "J7") (pin "4") (pinfunction "D1+_4") (pintype "bidirectional"))
    )
    (net (code "75") (name "XHDMI_TX2_N") (class "Default")
      (node (ref "IC3") (pin "22") (pinfunction "D2-_22") (pintype "bidirectional"))
      (node (ref "J3") (pin "35") (pinfunction "35_35") (pintype "bidirectional"))
      (node (ref "J7") (pin "3") (pinfunction "D2-_3") (pintype "bidirectional"))
    )
    (net (code "76") (name "XHDMI_TX2_P") (class "Default")
      (node (ref "IC3") (pin "23") (pinfunction "D2+_23") (pintype "bidirectional"))
      (node (ref "J3") (pin "36") (pinfunction "36_36") (pintype "bidirectional"))
      (node (ref "J7") (pin "1") (pinfunction "D2+_1") (pintype "bidirectional"))
    )
    (net (code "77") (name "XHDMI_TXC_N") (class "Default")
      (node (ref "IC3") (pin "15") (pinfunction "CLK-_15") (pintype "input"))
      (node (ref "J3") (pin "41") (pinfunction "41_41") (pintype "bidirectional"))
      (node (ref "J7") (pin "12") (pinfunction "CLK-_12") (pintype "bidirectional"))
    )
    (net (code "78") (name "XHDMI_TXC_P") (class "Default")
      (node (ref "IC3") (pin "16") (pinfunction "CLK+_16") (pintype "input"))
      (node (ref "J3") (pin "42") (pinfunction "42_42") (pintype "bidirectional"))
      (node (ref "J7") (pin "10") (pinfunction "CLK+_10") (pintype "bidirectional"))
    )
    (net (code "79") (name "XI2C_SCL0") (class "Default")
      (node (ref "J4") (pin "31") (pinfunction "31_31") (pintype "bidirectional"))
      (node (ref "SV1") (pin "27") (pinfunction "27_27") (pintype "passive"))
    )
    (net (code "80") (name "XI2C_SCL1") (class "Default")
      (node (ref "J4") (pin "29") (pinfunction "29_29") (pintype "bidirectional"))
      (node (ref "SV1") (pin "25") (pinfunction "25_25") (pintype "passive"))
    )
    (net (code "81") (name "XI2C_SCL2") (class "Default")
      (node (ref "J4") (pin "27") (pinfunction "27_27") (pintype "bidirectional"))
      (node (ref "SV1") (pin "23") (pinfunction "23_23") (pintype "passive"))
    )
    (net (code "82") (name "XI2C_SDA0") (class "Default")
      (node (ref "J4") (pin "32") (pinfunction "32_32") (pintype "bidirectional"))
      (node (ref "SV1") (pin "28") (pinfunction "28_28") (pintype "passive"))
    )
    (net (code "83") (name "XI2C_SDA1") (class "Default")
      (node (ref "J4") (pin "30") (pinfunction "30_30") (pintype "bidirectional"))
      (node (ref "SV1") (pin "26") (pinfunction "26_26") (pintype "passive"))
    )
    (net (code "84") (name "XI2C_SDA2") (class "Default")
      (node (ref "J4") (pin "28") (pinfunction "28_28") (pintype "bidirectional"))
      (node (ref "SV1") (pin "24") (pinfunction "24_24") (pintype "passive"))
    )
    (net (code "85") (name "XI2S0_BCLK") (class "Default")
      (node (ref "J4") (pin "19") (pinfunction "19_19") (pintype "bidirectional"))
      (node (ref "SV1") (pin "15") (pinfunction "15_15") (pintype "passive"))
    )
    (net (code "86") (name "XI2S0_DIN") (class "Default")
      (node (ref "J4") (pin "18") (pinfunction "18_18") (pintype "bidirectional"))
      (node (ref "SV1") (pin "14") (pinfunction "14_14") (pintype "passive"))
    )
    (net (code "87") (name "XI2S0_DOUT") (class "Default")
      (node (ref "J4") (pin "17") (pinfunction "17_17") (pintype "bidirectional"))
      (node (ref "SV1") (pin "13") (pinfunction "13_13") (pintype "passive"))
    )
    (net (code "88") (name "XI2S0_LRCLK") (class "Default")
      (node (ref "J4") (pin "15") (pinfunction "15_15") (pintype "bidirectional"))
      (node (ref "SV1") (pin "11") (pinfunction "11_11") (pintype "passive"))
    )
    (net (code "89") (name "XI2S0_MCLK") (class "Default")
      (node (ref "J4") (pin "20") (pinfunction "20_20") (pintype "bidirectional"))
      (node (ref "SV1") (pin "16") (pinfunction "16_16") (pintype "passive"))
    )
    (net (code "90") (name "XMIPICSI_D0_N") (class "Default")
      (node (ref "J3") (pin "11") (pinfunction "11_11") (pintype "bidirectional"))
    )
    (net (code "91") (name "XMIPICSI_D0_P") (class "Default")
      (node (ref "J3") (pin "12") (pinfunction "12_12") (pintype "bidirectional"))
    )
    (net (code "92") (name "XMIPICSI_D1_N") (class "Default")
      (node (ref "J3") (pin "13") (pinfunction "13_13") (pintype "bidirectional"))
    )
    (net (code "93") (name "XMIPICSI_D1_P") (class "Default")
      (node (ref "J3") (pin "14") (pinfunction "14_14") (pintype "bidirectional"))
    )
    (net (code "94") (name "XMIPICSI_D2_N") (class "Default")
      (node (ref "J3") (pin "15") (pinfunction "15_15") (pintype "bidirectional"))
    )
    (net (code "95") (name "XMIPICSI_D2_P") (class "Default")
      (node (ref "J3") (pin "16") (pinfunction "16_16") (pintype "bidirectional"))
    )
    (net (code "96") (name "XMIPICSI_D3_N") (class "Default")
      (node (ref "J3") (pin "17") (pinfunction "17_17") (pintype "bidirectional"))
    )
    (net (code "97") (name "XMIPICSI_D3_P") (class "Default")
      (node (ref "J3") (pin "18") (pinfunction "18_18") (pintype "bidirectional"))
    )
    (net (code "98") (name "XMIPICSI_DCLK_N") (class "Default")
      (node (ref "J3") (pin "9") (pinfunction "9_9") (pintype "bidirectional"))
    )
    (net (code "99") (name "XMIPICSI_DCLK_P") (class "Default")
      (node (ref "J3") (pin "10") (pinfunction "10_10") (pintype "bidirectional"))
    )
    (net (code "100") (name "XMIPIDSI_D0_N") (class "Default")
      (node (ref "J3") (pin "23") (pinfunction "23_23") (pintype "bidirectional"))
    )
    (net (code "101") (name "XMIPIDSI_D0_P") (class "Default")
      (node (ref "J3") (pin "24") (pinfunction "24_24") (pintype "bidirectional"))
    )
    (net (code "102") (name "XMIPIDSI_D1_N") (class "Default")
      (node (ref "J3") (pin "25") (pinfunction "25_25") (pintype "bidirectional"))
    )
    (net (code "103") (name "XMIPIDSI_D1_P") (class "Default")
      (node (ref "J3") (pin "26") (pinfunction "26_26") (pintype "bidirectional"))
    )
    (net (code "104") (name "XMIPIDSI_D2_N") (class "Default")
      (node (ref "J3") (pin "27") (pinfunction "27_27") (pintype "bidirectional"))
    )
    (net (code "105") (name "XMIPIDSI_D2_P") (class "Default")
      (node (ref "J3") (pin "28") (pinfunction "28_28") (pintype "bidirectional"))
    )
    (net (code "106") (name "XMIPIDSI_D3_N") (class "Default")
      (node (ref "J3") (pin "29") (pinfunction "29_29") (pintype "bidirectional"))
    )
    (net (code "107") (name "XMIPIDSI_D3_P") (class "Default")
      (node (ref "J3") (pin "30") (pinfunction "30_30") (pintype "bidirectional"))
    )
    (net (code "108") (name "XMIPIDSI_DCLK_N") (class "Default")
      (node (ref "J3") (pin "21") (pinfunction "21_21") (pintype "bidirectional"))
    )
    (net (code "109") (name "XMIPIDSI_DCLK_P") (class "Default")
      (node (ref "J3") (pin "22") (pinfunction "22_22") (pintype "bidirectional"))
    )
    (net (code "110") (name "XNRESET") (class "Default")
      (node (ref "J4") (pin "11") (pinfunction "11_11") (pintype "bidirectional"))
      (node (ref "R12") (pin "2") (pinfunction "2_2") (pintype "passive"))
    )
    (net (code "111") (name "XOTG_D_N") (class "Default")
      (node (ref "J2") (pin "D-") (pinfunction "D-_D-") (pintype "bidirectional"))
      (node (ref "J3") (pin "45") (pinfunction "45_45") (pintype "bidirectional"))
    )
    (net (code "112") (name "XOTG_D_P") (class "Default")
      (node (ref "J2") (pin "D+") (pinfunction "D+_D+") (pintype "bidirectional"))
      (node (ref "J3") (pin "46") (pinfunction "46_46") (pintype "bidirectional"))
    )
    (net (code "113") (name "XOTG_ID") (class "Default")
      (node (ref "J2") (pin "ID") (pinfunction "ID_ID") (pintype "bidirectional"))
      (node (ref "J3") (pin "50") (pinfunction "50_50") (pintype "bidirectional"))
      (node (ref "R14") (pin "1") (pinfunction "1_1") (pintype "passive"))
    )
    (net (code "114") (name "XPGC27") (class "Default")
      (node (ref "J4") (pin "62") (pinfunction "62_62") (pintype "bidirectional"))
    )
    (net (code "115") (name "XPWERKEY") (class "Default")
      (node (ref "J4") (pin "9") (pinfunction "9_9") (pintype "bidirectional"))
      (node (ref "R9") (pin "2") (pinfunction "2_2") (pintype "passive"))
    )
    (net (code "116") (name "XPWM0") (class "Default")
      (node (ref "J4") (pin "26") (pinfunction "26_26") (pintype "bidirectional"))
      (node (ref "SV1") (pin "22") (pinfunction "22_22") (pintype "passive"))
    )
    (net (code "117") (name "XPWM1") (class "Default")
      (node (ref "J4") (pin "25") (pinfunction "25_25") (pintype "bidirectional"))
      (node (ref "SV1") (pin "21") (pinfunction "21_21") (pintype "passive"))
    )
    (net (code "118") (name "XSD0_CLK") (class "Default")
      (node (ref "J4") (pin "49") (pinfunction "49_49") (pintype "bidirectional"))
    )
    (net (code "119") (name "XSD0_CMD") (class "Default")
      (node (ref "J4") (pin "47") (pinfunction "47_47") (pintype "bidirectional"))
    )
    (net (code "120") (name "XSD0_D0") (class "Default")
      (node (ref "J4") (pin "52") (pinfunction "52_52") (pintype "bidirectional"))
    )
    (net (code "121") (name "XSD0_D1") (class "Default")
      (node (ref "J4") (pin "51") (pinfunction "51_51") (pintype "bidirectional"))
    )
    (net (code "122") (name "XSD0_D2") (class "Default")
      (node (ref "J4") (pin "50") (pinfunction "50_50") (pintype "bidirectional"))
    )
    (net (code "123") (name "XSD0_D3") (class "Default")
      (node (ref "J4") (pin "48") (pinfunction "48_48") (pintype "bidirectional"))
    )
    (net (code "124") (name "XSPI_CLK") (class "Default")
      (node (ref "J4") (pin "23") (pinfunction "23_23") (pintype "bidirectional"))
      (node (ref "SV1") (pin "19") (pinfunction "19_19") (pintype "passive"))
    )
    (net (code "125") (name "XSPI_CS") (class "Default")
      (node (ref "J4") (pin "24") (pinfunction "24_24") (pintype "bidirectional"))
      (node (ref "SV1") (pin "20") (pinfunction "20_20") (pintype "passive"))
    )
    (net (code "126") (name "XSPI_MISO") (class "Default")
      (node (ref "J4") (pin "21") (pinfunction "21_21") (pintype "bidirectional"))
      (node (ref "SV1") (pin "17") (pinfunction "17_17") (pintype "passive"))
    )
    (net (code "127") (name "XSPI_MOSI") (class "Default")
      (node (ref "J4") (pin "22") (pinfunction "22_22") (pintype "bidirectional"))
      (node (ref "SV1") (pin "18") (pinfunction "18_18") (pintype "passive"))
    )
    (net (code "128") (name "XUART_RX0") (class "Default")
      (node (ref "J4") (pin "46") (pinfunction "46_46") (pintype "bidirectional"))
      (node (ref "SV1") (pin "36") (pinfunction "36_36") (pintype "passive"))
    )
    (net (code "129") (name "XUART_RX1") (class "Default")
      (node (ref "J4") (pin "44") (pinfunction "44_44") (pintype "bidirectional"))
      (node (ref "SV1") (pin "34") (pinfunction "34_34") (pintype "passive"))
    )
    (net (code "130") (name "XUART_TX0") (class "Default")
      (node (ref "J4") (pin "45") (pinfunction "45_45") (pintype "bidirectional"))
      (node (ref "SV1") (pin "35") (pinfunction "35_35") (pintype "passive"))
    )
    (net (code "131") (name "XUART_TX1") (class "Default")
      (node (ref "J4") (pin "43") (pinfunction "43_43") (pintype "bidirectional"))
      (node (ref "SV1") (pin "33") (pinfunction "33_33") (pintype "passive"))
    )
    (net (code "132") (name "XUSBH_D_N") (class "Default")
      (node (ref "J3") (pin "47") (pinfunction "47_47") (pintype "bidirectional"))
      (node (ref "J5") (pin "2") (pinfunction "D-_2") (pintype "bidirectional"))
    )
    (net (code "133") (name "XUSBH_D_P") (class "Default")
      (node (ref "J3") (pin "48") (pinfunction "48_48") (pintype "bidirectional"))
      (node (ref "J5") (pin "3") (pinfunction "D+_3") (pintype "bidirectional"))
    )
    (net (code "134") (name "XVDDPWRON") (class "Default")
      (node (ref "J4") (pin "38") (pinfunction "38_38") (pintype "bidirectional"))
      (node (ref "R15") (pin "2") (pinfunction "2_2") (pintype "passive"))
    )
    (net (code "135") (name "unconnected-(IC2-~{OC}-Pad3)") (class "Default")
      (node (ref "IC2") (pin "3") (pinfunction "~{OC}_3") (pintype "bidirectional"))
    )
    (net (code "136") (name "unconnected-(IC4-~{OC}-Pad3)") (class "Default")
      (node (ref "IC4") (pin "3") (pinfunction "~{OC}_3") (pintype "bidirectional"))
    )
    (net (code "137") (name "unconnected-(J3-Pad49)") (class "Default")
      (node (ref "J3") (pin "49") (pinfunction "49_49") (pintype "bidirectional"))
    )
    (net (code "138") (name "unconnected-(J3-Pad51)") (class "Default")
      (node (ref "J3") (pin "51") (pinfunction "51_51") (pintype "bidirectional"))
    )
    (net (code "139") (name "unconnected-(J3-Pad53)") (class "Default")
      (node (ref "J3") (pin "53") (pinfunction "53_53") (pintype "bidirectional"))
    )
    (net (code "140") (name "unconnected-(J3-Pad57)") (class "Default")
      (node (ref "J3") (pin "57") (pinfunction "57_57") (pintype "bidirectional"))
    )
    (net (code "141") (name "unconnected-(J3-Pad58)") (class "Default")
      (node (ref "J3") (pin "58") (pinfunction "58_58") (pintype "bidirectional"))
    )
    (net (code "142") (name "unconnected-(J3-Pad61)") (class "Default")
      (node (ref "J3") (pin "61") (pinfunction "61_61") (pintype "bidirectional"))
    )
    (net (code "143") (name "unconnected-(J3-Pad62)") (class "Default")
      (node (ref "J3") (pin "62") (pinfunction "62_62") (pintype "bidirectional"))
    )
    (net (code "144") (name "unconnected-(J4-Pad7)") (class "Default")
      (node (ref "J4") (pin "7") (pinfunction "7_7") (pintype "bidirectional"))
    )
    (net (code "145") (name "unconnected-(J4-Pad53)") (class "Default")
      (node (ref "J4") (pin "53") (pinfunction "53_53") (pintype "bidirectional"))
    )
    (net (code "146") (name "unconnected-(J4-Pad69)") (class "Default")
      (node (ref "J4") (pin "69") (pinfunction "69_69") (pintype "bidirectional"))
    )
    (net (code "147") (name "unconnected-(J6-1-PadDTR)") (class "Default")
      (node (ref "J6") (pin "DTR") (pinfunction "1_DTR") (pintype "passive"))
    )
    (net (code "148") (name "unconnected-(J6-4-PadVCC)") (class "Default")
      (node (ref "J6") (pin "VCC") (pinfunction "4_VCC") (pintype "passive"))
    )
    (net (code "149") (name "unconnected-(J6-5-PadCTS)") (class "Default")
      (node (ref "J6") (pin "CTS") (pinfunction "5_CTS") (pintype "passive"))
    )
    (net (code "150") (name "unconnected-(J7-UTILITY-Pad14)") (class "Default")
      (node (ref "J7") (pin "14") (pinfunction "UTILITY_14") (pintype "bidirectional"))
    )
    (net (code "151") (name "unconnected-(S3-Pad3)") (class "Default")
      (node (ref "S3") (pin "3") (pinfunction "3_3") (pintype "bidirectional"))
    )
    (net (code "152") (name "unconnected-(S3-Pad6)") (class "Default")
      (node (ref "S3") (pin "6") (pinfunction "6_6") (pintype "bidirectional"))
    )
  )
)
